# Motors_DCVs.net
KiCad netlist of a schematic drawn in Altium Designer
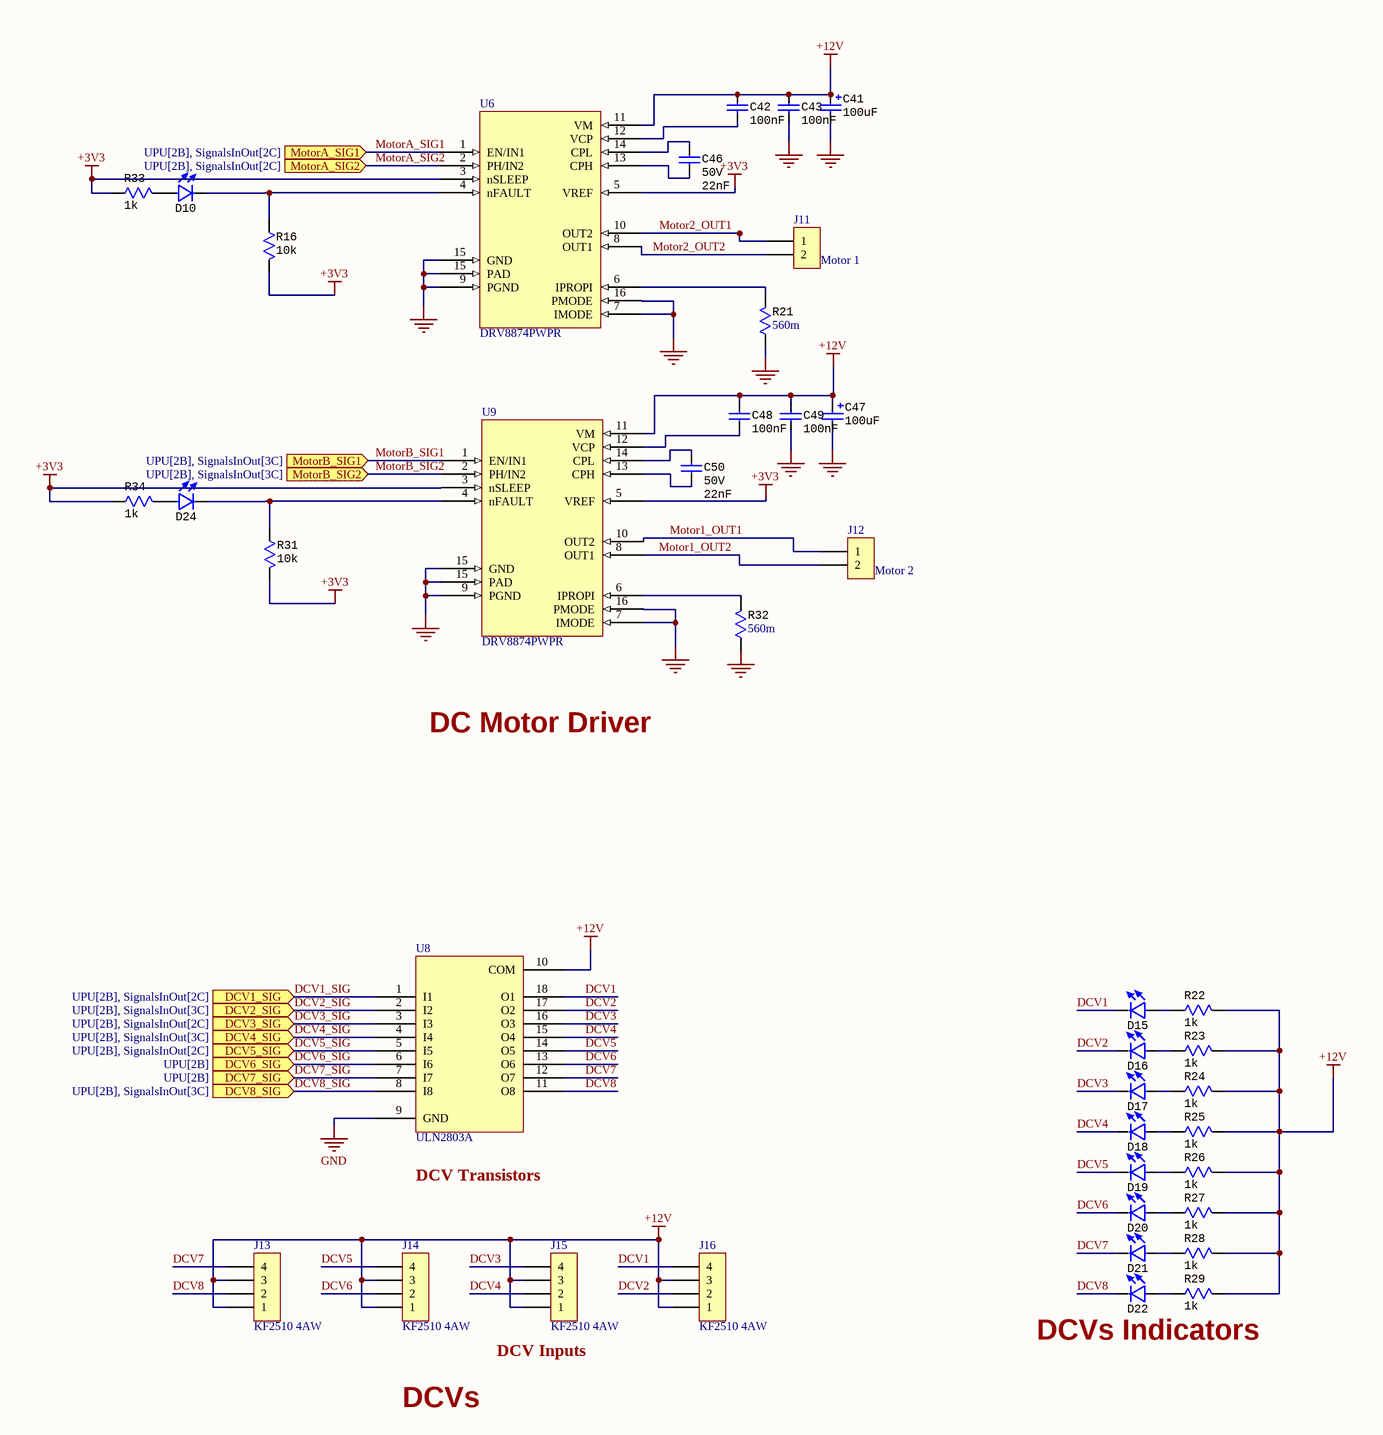
[diagram p0: Motors_DCVs.SchDoc]

(export (version "E")
  (design (tool "Eeschema 10.0.6"))
  (components
    (comp (ref "C41")
      (value "100uF")
      (footprint "CAP Electrolytic SMD G_10X10.3X10.2(CPOL-EU153CLV-1010)")
      (fields (field (name "MANUFACTURER") "ROQANG") (field (name "MANUFACTURER PART NUMBER") "RT1J101M1010"))
      (libsource (lib "Passive") (part "CAP ELEC 100uF 68V"))
    )
    (comp (ref "C42")
      (value "100nF")
      (footprint "CAP Ceramic SMD 0603")
      (description "0603 0.1 uF 100 V ±10% Tolerance X7R Multilayer Ceramic Capacitor")
      (fields
        (field (name "MANUFACTURER") "Yageo")
        (field (name "MANUFACTURER PART NUMBER") "AC0603KRX7R0BB104")
      )
      (libsource (lib "capacitor") (part "CAP 0603 100nF 100V"))
    )
    (comp (ref "C43")
      (value "100nF")
      (footprint "CAP Ceramic SMD 0603")
      (description "0603 0.1 uF 100 V ±10% Tolerance X7R Multilayer Ceramic Capacitor")
      (fields
        (field (name "MANUFACTURER") "Yageo")
        (field (name "MANUFACTURER PART NUMBER") "AC0603KRX7R0BB104")
      )
      (libsource (lib "capacitor") (part "CAP 0603 100nF 100V"))
    )
    (comp (ref "C46")
      (value "22nF")
      (footprint "CAP Ceramic SMD 0603")
      (description "Ceramic capacitor SMD-0603 22nF /50V X7R# K +-10%, Samsung, RoHS")
      (fields
        (field (name "MANUFACTURER") "Samsung")
        (field (name "MANUFACTURER PART NUMBER") "CL10B223KB8NNNC")
        (field (name "VOLTAGE") "50V")
        (field (name "CAPACITANCE") "22nF")
      )
      (libsource (lib "Passive") (part "CAP 0603 22nF 50V"))
    )
    (comp (ref "C47")
      (value "100uF")
      (footprint "CAP Electrolytic SMD G_10X10.3X10.2(CPOL-EU153CLV-1010)")
      (fields (field (name "MANUFACTURER") "ROQANG") (field (name "MANUFACTURER PART NUMBER") "RT1J101M1010"))
      (libsource (lib "Passive") (part "CAP ELEC 100uF 68V"))
    )
    (comp (ref "C48")
      (value "100nF")
      (footprint "CAP Ceramic SMD 0603")
      (description "0603 0.1 uF 100 V ±10% Tolerance X7R Multilayer Ceramic Capacitor")
      (fields
        (field (name "MANUFACTURER") "Yageo")
        (field (name "MANUFACTURER PART NUMBER") "AC0603KRX7R0BB104")
      )
      (libsource (lib "capacitor") (part "CAP 0603 100nF 100V"))
    )
    (comp (ref "C49")
      (value "100nF")
      (footprint "CAP Ceramic SMD 0603")
      (description "0603 0.1 uF 100 V ±10% Tolerance X7R Multilayer Ceramic Capacitor")
      (fields
        (field (name "MANUFACTURER") "Yageo")
        (field (name "MANUFACTURER PART NUMBER") "AC0603KRX7R0BB104")
      )
      (libsource (lib "capacitor") (part "CAP 0603 100nF 100V"))
    )
    (comp (ref "C50")
      (value "22nF")
      (footprint "CAP Ceramic SMD 0603")
      (description "Ceramic capacitor SMD-0603 22nF /50V X7R# K +-10%, Samsung, RoHS")
      (fields
        (field (name "MANUFACTURER") "Samsung")
        (field (name "MANUFACTURER PART NUMBER") "CL10B223KB8NNNC")
        (field (name "VOLTAGE") "50V")
        (field (name "CAPACITANCE") "22nF")
      )
      (libsource (lib "Passive") (part "CAP 0603 22nF 50V"))
    )
    (comp (ref "D10")
      (value "~")
      (footprint "LED SMD 0805R")
      (description "red 0805 Light Emitting Diodes (LED) ROHS")
      (fields
        (field (name "MANUFACTURER") "FOSHAN Nationstar Optoelectronics")
        (field (name "MANUFACTURER PART NUMBER") "NCD0805R1")
      )
      (libsource (lib "diode") (part "LED 0805 Red"))
    )
    (comp (ref "D15")
      (value "~")
      (footprint "LED SMD 0805G")
      (fields
        (field (name "MANUFACTURER") "FOSHAN Nationstar Optoelectronics")
        (field (name "MANUFACTURER PART NUMBER") "NCD0805G1")
      )
      (libsource (lib "diode") (part "LED 0805 Emerald"))
    )
    (comp (ref "D16")
      (value "~")
      (footprint "LED SMD 0805G")
      (fields
        (field (name "MANUFACTURER") "FOSHAN Nationstar Optoelectronics")
        (field (name "MANUFACTURER PART NUMBER") "NCD0805G1")
      )
      (libsource (lib "diode") (part "LED 0805 Emerald"))
    )
    (comp (ref "D17")
      (value "~")
      (footprint "LED SMD 0805G")
      (fields
        (field (name "MANUFACTURER") "FOSHAN Nationstar Optoelectronics")
        (field (name "MANUFACTURER PART NUMBER") "NCD0805G1")
      )
      (libsource (lib "diode") (part "LED 0805 Emerald"))
    )
    (comp (ref "D18")
      (value "~")
      (footprint "LED SMD 0805G")
      (fields
        (field (name "MANUFACTURER") "FOSHAN Nationstar Optoelectronics")
        (field (name "MANUFACTURER PART NUMBER") "NCD0805G1")
      )
      (libsource (lib "diode") (part "LED 0805 Emerald"))
    )
    (comp (ref "D19")
      (value "~")
      (footprint "LED SMD 0805G")
      (fields
        (field (name "MANUFACTURER") "FOSHAN Nationstar Optoelectronics")
        (field (name "MANUFACTURER PART NUMBER") "NCD0805G1")
      )
      (libsource (lib "diode") (part "LED 0805 Emerald"))
    )
    (comp (ref "D20")
      (value "~")
      (footprint "LED SMD 0805G")
      (fields
        (field (name "MANUFACTURER") "FOSHAN Nationstar Optoelectronics")
        (field (name "MANUFACTURER PART NUMBER") "NCD0805G1")
      )
      (libsource (lib "diode") (part "LED 0805 Emerald"))
    )
    (comp (ref "D21")
      (value "~")
      (footprint "LED SMD 0805G")
      (fields
        (field (name "MANUFACTURER") "FOSHAN Nationstar Optoelectronics")
        (field (name "MANUFACTURER PART NUMBER") "NCD0805G1")
      )
      (libsource (lib "diode") (part "LED 0805 Emerald"))
    )
    (comp (ref "D22")
      (value "~")
      (footprint "LED SMD 0805G")
      (fields
        (field (name "MANUFACTURER") "FOSHAN Nationstar Optoelectronics")
        (field (name "MANUFACTURER PART NUMBER") "NCD0805G1")
      )
      (libsource (lib "diode") (part "LED 0805 Emerald"))
    )
    (comp (ref "D24")
      (value "~")
      (footprint "LED SMD 0805R")
      (description "red 0805 Light Emitting Diodes (LED) ROHS")
      (fields
        (field (name "MANUFACTURER") "FOSHAN Nationstar Optoelectronics")
        (field (name "MANUFACTURER PART NUMBER") "NCD0805R1")
      )
      (libsource (lib "diode") (part "LED 0805 Red"))
    )
    (comp (ref "J11")
      (value "Motor 1")
      (footprint "Connector MOLEX KK-254 KF2510-2AW 2 90deg")
      (fields (field (name "MANUFACTURER") "CAX") (field (name "MANUFACTURERPARTNUMBER") "2510-2AW"))
      (libsource (lib "Signal connectors") (part "KF2510 2AW"))
    )
    (comp (ref "J12")
      (value "Motor 2")
      (footprint "Connector MOLEX KK-254 KF2510-2AW 2 90deg")
      (fields (field (name "MANUFACTURER") "CAX") (field (name "MANUFACTURERPARTNUMBER") "2510-2AW"))
      (libsource (lib "Signal connectors") (part "KF2510 2AW"))
    )
    (comp (ref "J13")
      (value "KF2510 4AW")
      (footprint "Connector MOLEX KK-254 KF2510-4AW 4 90deg")
      (fields (field (name "MANUFACTURER") "CAX") (field (name "MANUFACTURERPARTNUMBER") "2510-4AW"))
      (libsource (lib "Signal connectors") (part "KF2510 4AW"))
    )
    (comp (ref "J14")
      (value "KF2510 4AW")
      (footprint "Connector MOLEX KK-254 KF2510-4AW 4 90deg")
      (fields (field (name "MANUFACTURER") "CAX") (field (name "MANUFACTURERPARTNUMBER") "2510-4AW"))
      (libsource (lib "Signal connectors") (part "KF2510 4AW"))
    )
    (comp (ref "J15")
      (value "KF2510 4AW")
      (footprint "Connector MOLEX KK-254 KF2510-4AW 4 90deg")
      (fields (field (name "MANUFACTURER") "CAX") (field (name "MANUFACTURERPARTNUMBER") "2510-4AW"))
      (libsource (lib "Signal connectors") (part "KF2510 4AW"))
    )
    (comp (ref "J16")
      (value "KF2510 4AW")
      (footprint "Connector MOLEX KK-254 KF2510-4AW 4 90deg")
      (fields (field (name "MANUFACTURER") "CAX") (field (name "MANUFACTURERPARTNUMBER") "2510-4AW"))
      (libsource (lib "Signal connectors") (part "KF2510 4AW"))
    )
    (comp (ref "R16")
      (value "10k")
      (footprint "RES SMD 0603")
      (description "Res Thick Film 0603 10K Ohm 1% 1/10W ±100ppm/°C Molded SMD Punched Carrier T/R")
      (fields
        (field (name "MANUFACTURER") "Panasonic")
        (field (name "MANUFACTURER PART NUMBER") "ERJ-3EKF1002V")
      )
      (libsource (lib "Passive") (part "RES 0603 10k 1%"))
    )
    (comp (ref "R21")
      (value "560m")
      (footprint "RES SMD 0603")
      (description "250mW Thick Film Resistors ±5% ±300ppm/℃ 560mΩ 0603 Chip Resistor - Surface Mount ROHS")
      (fields (field (name "TOLERANCE") "5%") (field (name "MANUFACTURER") "Panasonic"))
      (libsource (lib "Passive") (part "RES 0603 560m 5%"))
    )
    (comp (ref "R22")
      (value "1k")
      (footprint "RES SMD 0603")
      (description "Res Thick Film 0603 1K Ohm 1% 1/10W ±100ppm/°C Molded SMD Punched Carrier T/R")
      (fields
        (field (name "MANUFACTURER") "Panasonic")
        (field (name "MANUFACTURER PART NUMBER") "ERJ3EKF1001V")
      )
      (libsource (lib "Passive") (part "RES 0603 1k 1%"))
    )
    (comp (ref "R23")
      (value "1k")
      (footprint "RES SMD 0603")
      (description "Res Thick Film 0603 1K Ohm 1% 1/10W ±100ppm/°C Molded SMD Punched Carrier T/R")
      (fields
        (field (name "MANUFACTURER") "Panasonic")
        (field (name "MANUFACTURER PART NUMBER") "ERJ3EKF1001V")
      )
      (libsource (lib "Passive") (part "RES 0603 1k 1%"))
    )
    (comp (ref "R24")
      (value "1k")
      (footprint "RES SMD 0603")
      (description "Res Thick Film 0603 1K Ohm 1% 1/10W ±100ppm/°C Molded SMD Punched Carrier T/R")
      (fields
        (field (name "MANUFACTURER") "Panasonic")
        (field (name "MANUFACTURER PART NUMBER") "ERJ3EKF1001V")
      )
      (libsource (lib "Passive") (part "RES 0603 1k 1%"))
    )
    (comp (ref "R25")
      (value "1k")
      (footprint "RES SMD 0603")
      (description "Res Thick Film 0603 1K Ohm 1% 1/10W ±100ppm/°C Molded SMD Punched Carrier T/R")
      (fields
        (field (name "MANUFACTURER") "Panasonic")
        (field (name "MANUFACTURER PART NUMBER") "ERJ3EKF1001V")
      )
      (libsource (lib "Passive") (part "RES 0603 1k 1%"))
    )
    (comp (ref "R26")
      (value "1k")
      (footprint "RES SMD 0603")
      (description "Res Thick Film 0603 1K Ohm 1% 1/10W ±100ppm/°C Molded SMD Punched Carrier T/R")
      (fields
        (field (name "MANUFACTURER") "Panasonic")
        (field (name "MANUFACTURER PART NUMBER") "ERJ3EKF1001V")
      )
      (libsource (lib "Passive") (part "RES 0603 1k 1%"))
    )
    (comp (ref "R27")
      (value "1k")
      (footprint "RES SMD 0603")
      (description "Res Thick Film 0603 1K Ohm 1% 1/10W ±100ppm/°C Molded SMD Punched Carrier T/R")
      (fields
        (field (name "MANUFACTURER") "Panasonic")
        (field (name "MANUFACTURER PART NUMBER") "ERJ3EKF1001V")
      )
      (libsource (lib "Passive") (part "RES 0603 1k 1%"))
    )
    (comp (ref "R28")
      (value "1k")
      (footprint "RES SMD 0603")
      (description "Res Thick Film 0603 1K Ohm 1% 1/10W ±100ppm/°C Molded SMD Punched Carrier T/R")
      (fields
        (field (name "MANUFACTURER") "Panasonic")
        (field (name "MANUFACTURER PART NUMBER") "ERJ3EKF1001V")
      )
      (libsource (lib "Passive") (part "RES 0603 1k 1%"))
    )
    (comp (ref "R29")
      (value "1k")
      (footprint "RES SMD 0603")
      (description "Res Thick Film 0603 1K Ohm 1% 1/10W ±100ppm/°C Molded SMD Punched Carrier T/R")
      (fields
        (field (name "MANUFACTURER") "Panasonic")
        (field (name "MANUFACTURER PART NUMBER") "ERJ3EKF1001V")
      )
      (libsource (lib "Passive") (part "RES 0603 1k 1%"))
    )
    (comp (ref "R31")
      (value "10k")
      (footprint "RES SMD 0603")
      (description "Res Thick Film 0603 10K Ohm 1% 1/10W ±100ppm/°C Molded SMD Punched Carrier T/R")
      (fields
        (field (name "MANUFACTURER") "Panasonic")
        (field (name "MANUFACTURER PART NUMBER") "ERJ-3EKF1002V")
      )
      (libsource (lib "Passive") (part "RES 0603 10k 1%"))
    )
    (comp (ref "R32")
      (value "560m")
      (footprint "RES SMD 0603")
      (description "250mW Thick Film Resistors ±5% ±300ppm/℃ 560mΩ 0603 Chip Resistor - Surface Mount ROHS")
      (fields (field (name "TOLERANCE") "5%") (field (name "MANUFACTURER") "Panasonic"))
      (libsource (lib "Passive") (part "RES 0603 560m 5%"))
    )
    (comp (ref "R33")
      (value "1k")
      (footprint "RES SMD 0603")
      (description "Res Thick Film 0603 1K Ohm 1% 1/10W ±100ppm/°C Molded SMD Punched Carrier T/R")
      (fields
        (field (name "MANUFACTURER") "Panasonic")
        (field (name "MANUFACTURER PART NUMBER") "ERJ3EKF1001V")
      )
      (libsource (lib "Passive") (part "RES 0603 1k 1%"))
    )
    (comp (ref "R34")
      (value "1k")
      (footprint "RES SMD 0603")
      (description "Res Thick Film 0603 1K Ohm 1% 1/10W ±100ppm/°C Molded SMD Punched Carrier T/R")
      (fields
        (field (name "MANUFACTURER") "Panasonic")
        (field (name "MANUFACTURER PART NUMBER") "ERJ3EKF1001V")
      )
      (libsource (lib "Passive") (part "RES 0603 1k 1%"))
    )
    (comp (ref "U6")
      (value "DRV8874PWPR")
      (footprint "DRV8874PWPR")
      (description "40-V, 6-A H-bridge motor driver with integrated current sensing feedback 16-HTSSOP -40 to 125")
      (fields (field (name "MANUFACTURER") "Texas Instruments"))
      (libsource (lib "PMIC") (part "DRV8874PWPR"))
    )
    (comp (ref "U8")
      (value "ULN2803A")
      (footprint "ULN2803A")
      (description "SOP-18-300mil Darlington Transistor Arrays ROHS")
      (fields (field (name "MANUFACTURER") "UMW"))
      (libsource (lib "BackupLib") (part "ULN2803A"))
    )
    (comp (ref "U9")
      (value "DRV8874PWPR")
      (footprint "DRV8874PWPR")
      (description "40-V, 6-A H-bridge motor driver with integrated current sensing feedback 16-HTSSOP -40 to 125")
      (fields (field (name "MANUFACTURER") "Texas Instruments"))
      (libsource (lib "PMIC") (part "DRV8874PWPR"))
    )
  )
  (nets
    (net (code "1") (name "+3V3") (class "Default")
      (node (ref "R16") (pin "2") (pinfunction "2_2") (pintype "passive"))
      (node (ref "R31") (pin "2") (pinfunction "2_2") (pintype "passive"))
      (node (ref "R33") (pin "1") (pinfunction "1_1") (pintype "passive"))
      (node (ref "R34") (pin "1") (pinfunction "1_1") (pintype "passive"))
      (node (ref "U6") (pin "3") (pinfunction "nSLEEP_3") (pintype "input"))
      (node (ref "U6") (pin "5") (pinfunction "VREF_5") (pintype "input"))
      (node (ref "U9") (pin "3") (pinfunction "nSLEEP_3") (pintype "input"))
      (node (ref "U9") (pin "5") (pinfunction "VREF_5") (pintype "input"))
    )
    (net (code "2") (name "+12V") (class "Default")
      (node (ref "C41") (pin "1") (pinfunction "1_1") (pintype "passive"))
      (node (ref "C42") (pin "1") (pinfunction "1_1") (pintype "passive"))
      (node (ref "C43") (pin "1") (pinfunction "1_1") (pintype "passive"))
      (node (ref "C47") (pin "1") (pinfunction "1_1") (pintype "passive"))
      (node (ref "C48") (pin "1") (pinfunction "1_1") (pintype "passive"))
      (node (ref "C49") (pin "1") (pinfunction "1_1") (pintype "passive"))
      (node (ref "J13") (pin "1") (pinfunction "1_1") (pintype "passive"))
      (node (ref "J13") (pin "3") (pinfunction "3_3") (pintype "passive"))
      (node (ref "J14") (pin "1") (pinfunction "1_1") (pintype "passive"))
      (node (ref "J14") (pin "3") (pinfunction "3_3") (pintype "passive"))
      (node (ref "J15") (pin "1") (pinfunction "1_1") (pintype "passive"))
      (node (ref "J15") (pin "3") (pinfunction "3_3") (pintype "passive"))
      (node (ref "J16") (pin "1") (pinfunction "1_1") (pintype "passive"))
      (node (ref "J16") (pin "3") (pinfunction "3_3") (pintype "passive"))
      (node (ref "R22") (pin "2") (pinfunction "2_2") (pintype "passive"))
      (node (ref "R23") (pin "2") (pinfunction "2_2") (pintype "passive"))
      (node (ref "R24") (pin "2") (pinfunction "2_2") (pintype "passive"))
      (node (ref "R25") (pin "2") (pinfunction "2_2") (pintype "passive"))
      (node (ref "R26") (pin "2") (pinfunction "2_2") (pintype "passive"))
      (node (ref "R27") (pin "2") (pinfunction "2_2") (pintype "passive"))
      (node (ref "R28") (pin "2") (pinfunction "2_2") (pintype "passive"))
      (node (ref "R29") (pin "2") (pinfunction "2_2") (pintype "passive"))
      (node (ref "U6") (pin "11") (pinfunction "VM_11") (pintype "input"))
      (node (ref "U8") (pin "10") (pinfunction "COM_10") (pintype "passive"))
      (node (ref "U9") (pin "11") (pinfunction "VM_11") (pintype "input"))
    )
    (net (code "3") (name "/DCV1") (class "Default")
      (node (ref "D15") (pin "2") (pinfunction "2_2") (pintype "passive"))
      (node (ref "J16") (pin "4") (pinfunction "4_4") (pintype "passive"))
      (node (ref "U8") (pin "18") (pinfunction "O1_18") (pintype "passive"))
    )
    (net (code "4") (name "/DCV1_SIG") (class "Default")
      (node (ref "U8") (pin "1") (pinfunction "I1_1") (pintype "passive"))
    )
    (net (code "5") (name "/DCV2") (class "Default")
      (node (ref "D16") (pin "2") (pinfunction "2_2") (pintype "passive"))
      (node (ref "J16") (pin "2") (pinfunction "2_2") (pintype "passive"))
      (node (ref "U8") (pin "17") (pinfunction "O2_17") (pintype "passive"))
    )
    (net (code "6") (name "/DCV2_SIG") (class "Default")
      (node (ref "U8") (pin "2") (pinfunction "I2_2") (pintype "passive"))
    )
    (net (code "7") (name "/DCV3") (class "Default")
      (node (ref "D17") (pin "2") (pinfunction "2_2") (pintype "passive"))
      (node (ref "J15") (pin "4") (pinfunction "4_4") (pintype "passive"))
      (node (ref "U8") (pin "16") (pinfunction "O3_16") (pintype "passive"))
    )
    (net (code "8") (name "/DCV3_SIG") (class "Default")
      (node (ref "U8") (pin "3") (pinfunction "I3_3") (pintype "passive"))
    )
    (net (code "9") (name "/DCV4") (class "Default")
      (node (ref "D18") (pin "2") (pinfunction "2_2") (pintype "passive"))
      (node (ref "J15") (pin "2") (pinfunction "2_2") (pintype "passive"))
      (node (ref "U8") (pin "15") (pinfunction "O4_15") (pintype "passive"))
    )
    (net (code "10") (name "/DCV4_SIG") (class "Default")
      (node (ref "U8") (pin "4") (pinfunction "I4_4") (pintype "passive"))
    )
    (net (code "11") (name "/DCV5") (class "Default")
      (node (ref "D19") (pin "2") (pinfunction "2_2") (pintype "passive"))
      (node (ref "J14") (pin "4") (pinfunction "4_4") (pintype "passive"))
      (node (ref "U8") (pin "14") (pinfunction "O5_14") (pintype "passive"))
    )
    (net (code "12") (name "/DCV5_SIG") (class "Default")
      (node (ref "U8") (pin "5") (pinfunction "I5_5") (pintype "passive"))
    )
    (net (code "13") (name "/DCV6") (class "Default")
      (node (ref "D20") (pin "2") (pinfunction "2_2") (pintype "passive"))
      (node (ref "J14") (pin "2") (pinfunction "2_2") (pintype "passive"))
      (node (ref "U8") (pin "13") (pinfunction "O6_13") (pintype "passive"))
    )
    (net (code "14") (name "/DCV6_SIG") (class "Default")
      (node (ref "U8") (pin "6") (pinfunction "I6_6") (pintype "passive"))
    )
    (net (code "15") (name "/DCV7") (class "Default")
      (node (ref "D21") (pin "2") (pinfunction "2_2") (pintype "passive"))
      (node (ref "J13") (pin "4") (pinfunction "4_4") (pintype "passive"))
      (node (ref "U8") (pin "12") (pinfunction "O7_12") (pintype "passive"))
    )
    (net (code "16") (name "/DCV7_SIG") (class "Default")
      (node (ref "U8") (pin "7") (pinfunction "I7_7") (pintype "passive"))
    )
    (net (code "17") (name "/DCV8") (class "Default")
      (node (ref "D22") (pin "2") (pinfunction "2_2") (pintype "passive"))
      (node (ref "J13") (pin "2") (pinfunction "2_2") (pintype "passive"))
      (node (ref "U8") (pin "11") (pinfunction "O8_11") (pintype "passive"))
    )
    (net (code "18") (name "/DCV8_SIG") (class "Default")
      (node (ref "U8") (pin "8") (pinfunction "I8_8") (pintype "passive"))
    )
    (net (code "19") (name "/Motor1_OUT1") (class "Default")
      (node (ref "J12") (pin "1") (pinfunction "1_1") (pintype "passive"))
      (node (ref "U9") (pin "10") (pinfunction "OUT2_10") (pintype "input"))
    )
    (net (code "20") (name "/Motor1_OUT2") (class "Default")
      (node (ref "J12") (pin "2") (pinfunction "2_2") (pintype "passive"))
      (node (ref "U9") (pin "8") (pinfunction "OUT1_8") (pintype "input"))
    )
    (net (code "21") (name "/Motor2_OUT1") (class "Default")
      (node (ref "J11") (pin "1") (pinfunction "1_1") (pintype "passive"))
      (node (ref "U6") (pin "10") (pinfunction "OUT2_10") (pintype "input"))
    )
    (net (code "22") (name "/Motor2_OUT2") (class "Default")
      (node (ref "J11") (pin "2") (pinfunction "2_2") (pintype "passive"))
      (node (ref "U6") (pin "8") (pinfunction "OUT1_8") (pintype "input"))
    )
    (net (code "23") (name "/MotorA_SIG1") (class "Default")
      (node (ref "U6") (pin "1") (pinfunction "EN/IN1_1") (pintype "input"))
    )
    (net (code "24") (name "/MotorA_SIG2") (class "Default")
      (node (ref "U6") (pin "2") (pinfunction "PH/IN2_2") (pintype "input"))
    )
    (net (code "25") (name "/MotorB_SIG1") (class "Default")
      (node (ref "U9") (pin "1") (pinfunction "EN/IN1_1") (pintype "input"))
    )
    (net (code "26") (name "/MotorB_SIG2") (class "Default")
      (node (ref "U9") (pin "2") (pinfunction "PH/IN2_2") (pintype "input"))
    )
    (net (code "27") (name "GND") (class "Default")
      (node (ref "C41") (pin "2") (pinfunction "2_2") (pintype "passive"))
      (node (ref "C43") (pin "2") (pinfunction "2_2") (pintype "passive"))
      (node (ref "C47") (pin "2") (pinfunction "2_2") (pintype "passive"))
      (node (ref "C49") (pin "2") (pinfunction "2_2") (pintype "passive"))
      (node (ref "R21") (pin "1") (pinfunction "1_1") (pintype "passive"))
      (node (ref "R32") (pin "1") (pinfunction "1_1") (pintype "passive"))
      (node (ref "U6") (pin "15") (pinfunction "GND_15") (pintype "input"))
      (node (ref "U6") (pin "16") (pinfunction "PMODE_16") (pintype "input"))
      (node (ref "U6") (pin "7") (pinfunction "IMODE_7") (pintype "input"))
      (node (ref "U6") (pin "9") (pinfunction "PGND_9") (pintype "input"))
      (node (ref "U8") (pin "9") (pinfunction "GND_9") (pintype "passive"))
      (node (ref "U9") (pin "15") (pinfunction "PAD_15") (pintype "input"))
      (node (ref "U9") (pin "16") (pinfunction "PMODE_16") (pintype "input"))
      (node (ref "U9") (pin "7") (pinfunction "IMODE_7") (pintype "input"))
      (node (ref "U9") (pin "9") (pinfunction "PGND_9") (pintype "input"))
    )
    (net (code "28") (name "Net-(D10-Pad1)") (class "Default")
      (node (ref "D10") (pin "1") (pinfunction "1_1") (pintype "passive"))
      (node (ref "R33") (pin "2") (pinfunction "2_2") (pintype "passive"))
    )
    (net (code "29") (name "Net-(D15-Pad1)") (class "Default")
      (node (ref "D15") (pin "1") (pinfunction "1_1") (pintype "passive"))
      (node (ref "R22") (pin "1") (pinfunction "1_1") (pintype "passive"))
    )
    (net (code "30") (name "Net-(D16-Pad1)") (class "Default")
      (node (ref "D16") (pin "1") (pinfunction "1_1") (pintype "passive"))
      (node (ref "R23") (pin "1") (pinfunction "1_1") (pintype "passive"))
    )
    (net (code "31") (name "Net-(D17-Pad1)") (class "Default")
      (node (ref "D17") (pin "1") (pinfunction "1_1") (pintype "passive"))
      (node (ref "R24") (pin "1") (pinfunction "1_1") (pintype "passive"))
    )
    (net (code "32") (name "Net-(D18-Pad1)") (class "Default")
      (node (ref "D18") (pin "1") (pinfunction "1_1") (pintype "passive"))
      (node (ref "R25") (pin "1") (pinfunction "1_1") (pintype "passive"))
    )
    (net (code "33") (name "Net-(D19-Pad1)") (class "Default")
      (node (ref "D19") (pin "1") (pinfunction "1_1") (pintype "passive"))
      (node (ref "R26") (pin "1") (pinfunction "1_1") (pintype "passive"))
    )
    (net (code "34") (name "Net-(D20-Pad1)") (class "Default")
      (node (ref "D20") (pin "1") (pinfunction "1_1") (pintype "passive"))
      (node (ref "R27") (pin "1") (pinfunction "1_1") (pintype "passive"))
    )
    (net (code "35") (name "Net-(D21-Pad1)") (class "Default")
      (node (ref "D21") (pin "1") (pinfunction "1_1") (pintype "passive"))
      (node (ref "R28") (pin "1") (pinfunction "1_1") (pintype "passive"))
    )
    (net (code "36") (name "Net-(D22-Pad1)") (class "Default")
      (node (ref "D22") (pin "1") (pinfunction "1_1") (pintype "passive"))
      (node (ref "R29") (pin "1") (pinfunction "1_1") (pintype "passive"))
    )
    (net (code "37") (name "Net-(D24-Pad1)") (class "Default")
      (node (ref "D24") (pin "1") (pinfunction "1_1") (pintype "passive"))
      (node (ref "R34") (pin "2") (pinfunction "2_2") (pintype "passive"))
    )
    (net (code "38") (name "Net-(U6-CPH)") (class "Default")
      (node (ref "C46") (pin "2") (pinfunction "2_2") (pintype "passive"))
      (node (ref "U6") (pin "13") (pinfunction "CPH_13") (pintype "input"))
    )
    (net (code "39") (name "Net-(U6-CPL)") (class "Default")
      (node (ref "C46") (pin "1") (pinfunction "1_1") (pintype "passive"))
      (node (ref "U6") (pin "14") (pinfunction "CPL_14") (pintype "input"))
    )
    (net (code "40") (name "Net-(U6-IPROPI)") (class "Default")
      (node (ref "R21") (pin "2") (pinfunction "2_2") (pintype "passive"))
      (node (ref "U6") (pin "6") (pinfunction "IPROPI_6") (pintype "input"))
    )
    (net (code "41") (name "Net-(U6-VCP)") (class "Default")
      (node (ref "C42") (pin "2") (pinfunction "2_2") (pintype "passive"))
      (node (ref "U6") (pin "12") (pinfunction "VCP_12") (pintype "input"))
    )
    (net (code "42") (name "Net-(U6-nFAULT)") (class "Default")
      (node (ref "D10") (pin "2") (pinfunction "2_2") (pintype "passive"))
      (node (ref "R16") (pin "1") (pinfunction "1_1") (pintype "passive"))
      (node (ref "U6") (pin "4") (pinfunction "nFAULT_4") (pintype "input"))
    )
    (net (code "43") (name "Net-(U9-CPH)") (class "Default")
      (node (ref "C50") (pin "2") (pinfunction "2_2") (pintype "passive"))
      (node (ref "U9") (pin "13") (pinfunction "CPH_13") (pintype "input"))
    )
    (net (code "44") (name "Net-(U9-CPL)") (class "Default")
      (node (ref "C50") (pin "1") (pinfunction "1_1") (pintype "passive"))
      (node (ref "U9") (pin "14") (pinfunction "CPL_14") (pintype "input"))
    )
    (net (code "45") (name "Net-(U9-IPROPI)") (class "Default")
      (node (ref "R32") (pin "2") (pinfunction "2_2") (pintype "passive"))
      (node (ref "U9") (pin "6") (pinfunction "IPROPI_6") (pintype "input"))
    )
    (net (code "46") (name "Net-(U9-VCP)") (class "Default")
      (node (ref "C48") (pin "2") (pinfunction "2_2") (pintype "passive"))
      (node (ref "U9") (pin "12") (pinfunction "VCP_12") (pintype "input"))
    )
    (net (code "47") (name "Net-(U9-nFAULT)") (class "Default")
      (node (ref "D24") (pin "2") (pinfunction "2_2") (pintype "passive"))
      (node (ref "R31") (pin "1") (pinfunction "1_1") (pintype "passive"))
      (node (ref "U9") (pin "4") (pinfunction "nFAULT_4") (pintype "input"))
    )
  )
)
